# Connectors.net
KiCad netlist of a schematic drawn in Altium Designer
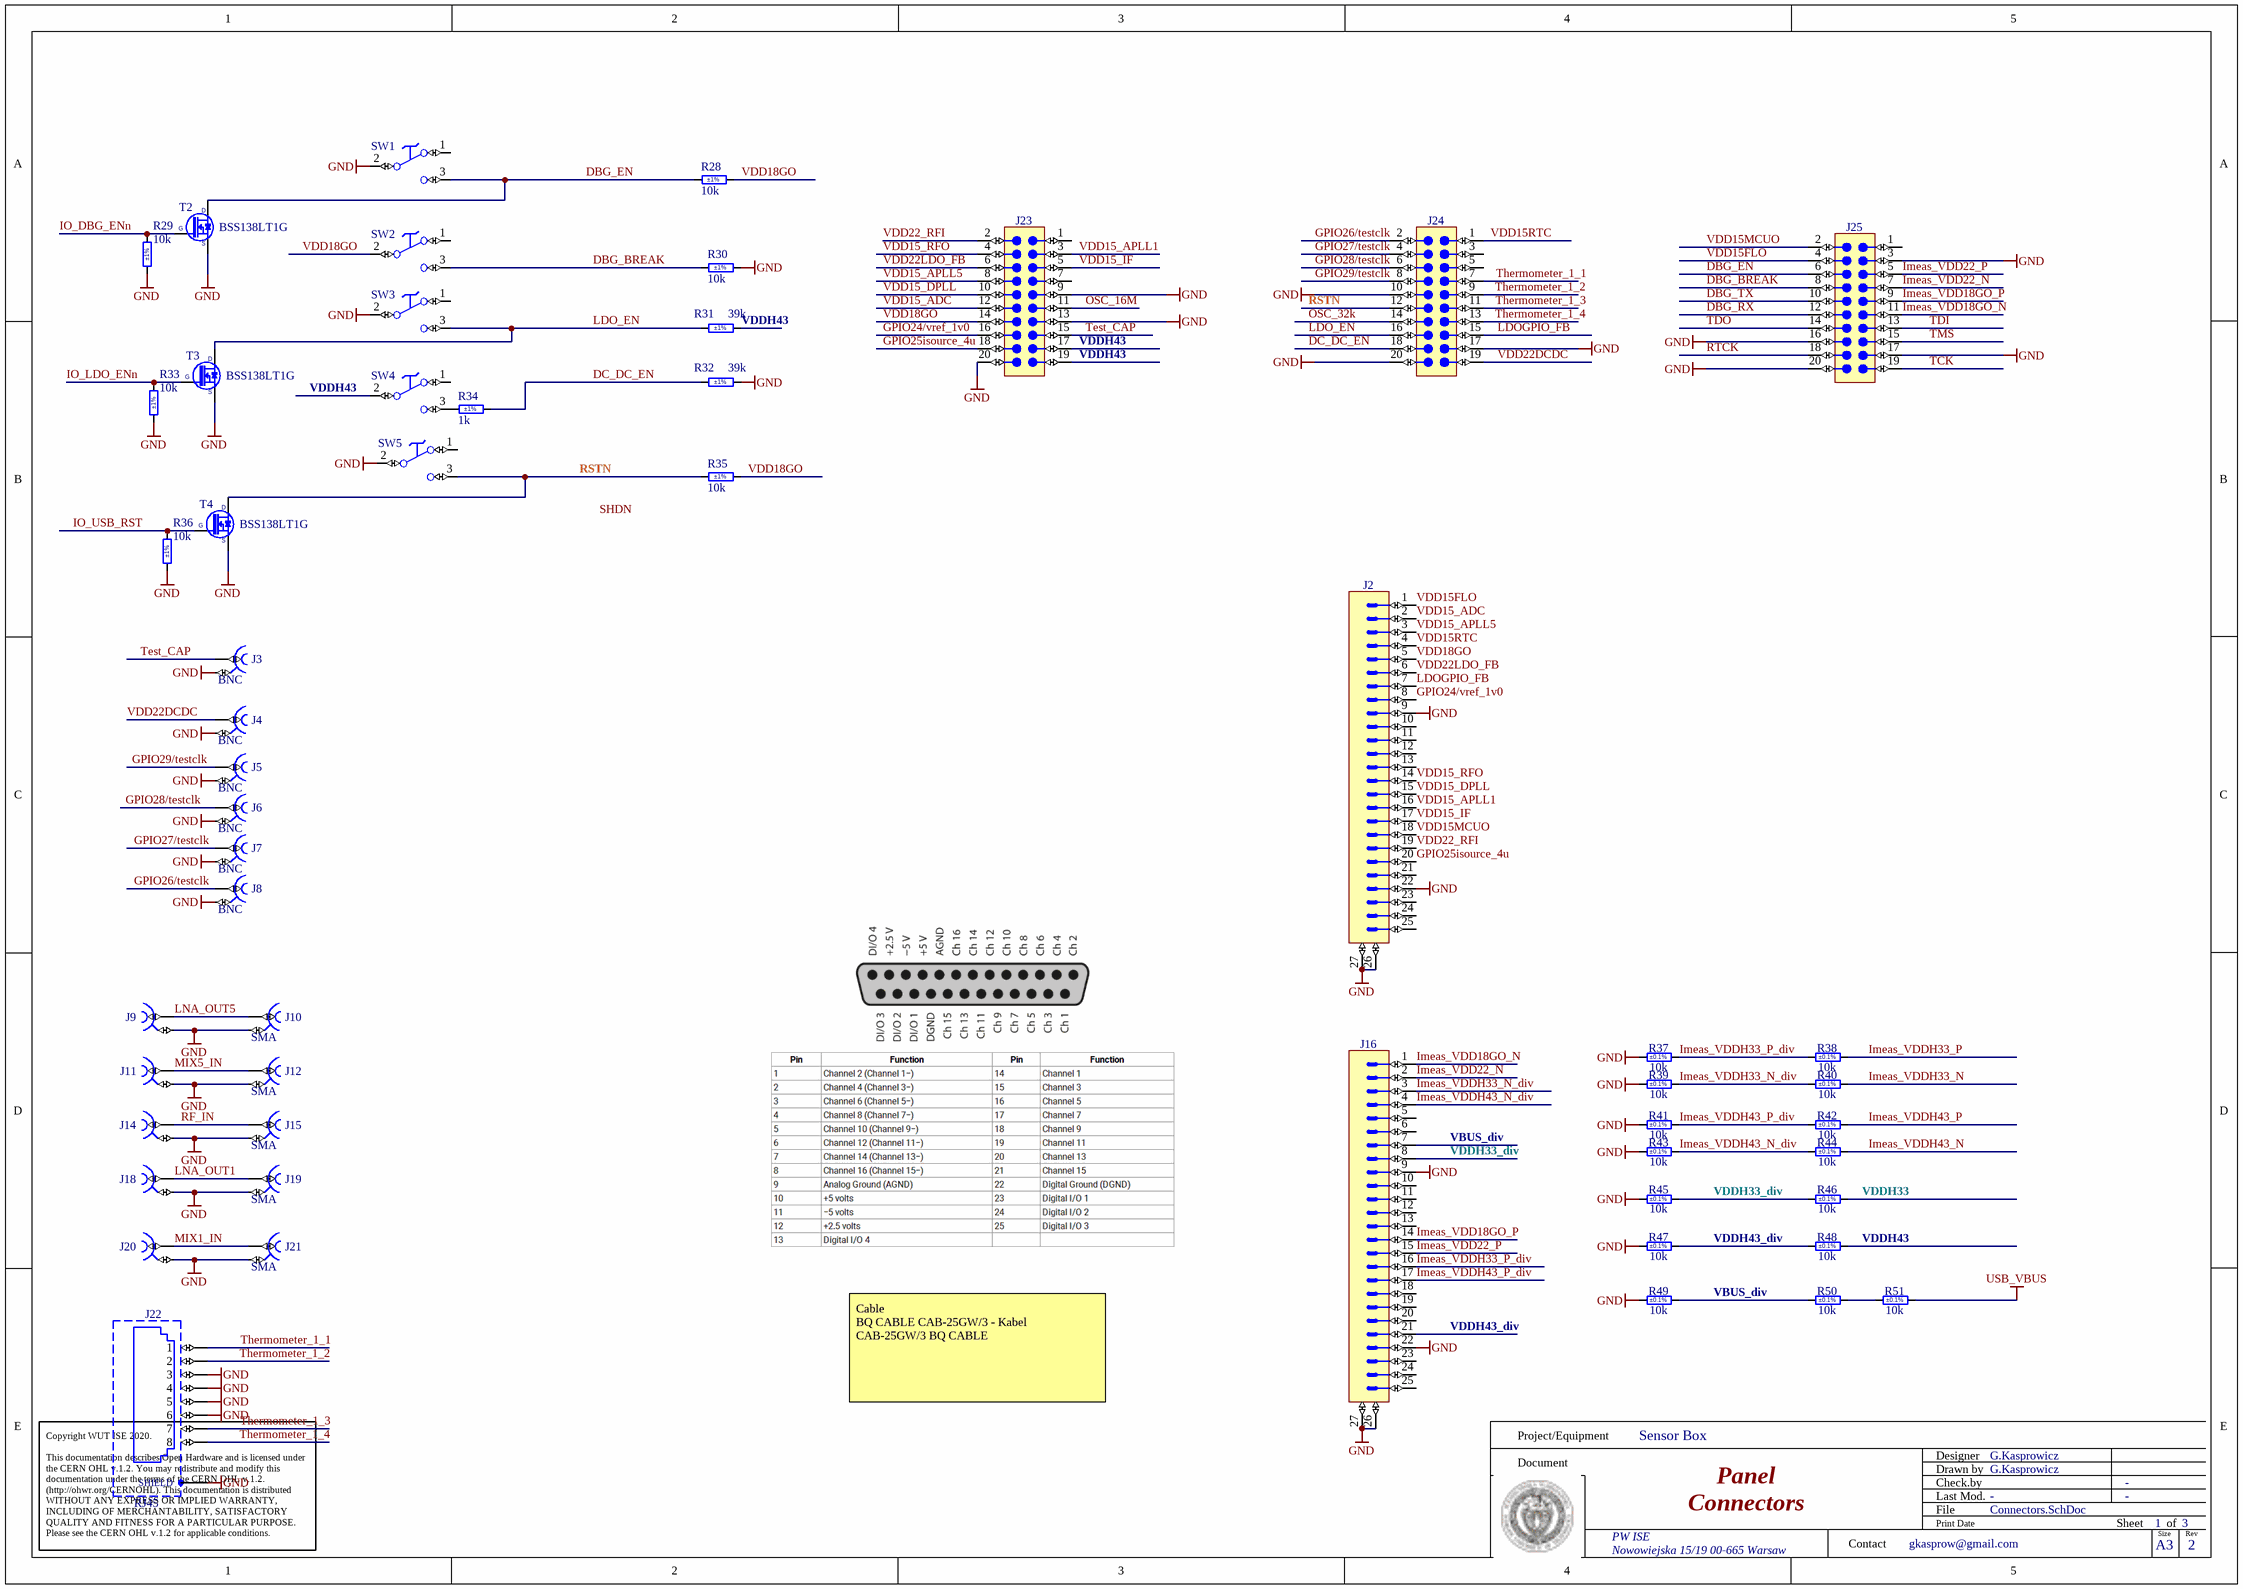
[diagram p0: Connectors.SchDoc]

(export (version "E")
  (design (tool "Eeschema 10.0.6"))
  (components
    (comp (ref "J2")
      (value "D-Sub")
      (footprint "AMPHENOL_L717SDBH25POL2RM8C309")
      (description "Connector D-sub 25 Male")
      (fields
        (field (name "PART NUMBER") "AMPHENOL_L717SDBH25POL2RM8C309")
        (field (name "MANUFACTURER") "AMPHENOL")
        (field (name "AUTHOR") "CERN DEM BC")
      )
      (libsource (lib "Connectors") (part "Connector D-sub 25 Male"))
    )
    (comp (ref "J3")
      (value "BNC")
      (footprint "TYCO_5-1634506-1")
      (fields
        (field (name "PART NUMBER") "TYCO_5-1634506-1")
        (field (name "MANUFACTURER") "TYCO ELECTRONICS")
        (field (name "MANUFACTURER PART NUMBER") "5-1634506-1")
        (field (name "AUTHOR") "CERN DEM JLC")
      )
      (libsource (lib "Connectors") (part "Coax_1Female_1Shield"))
    )
    (comp (ref "J4")
      (value "BNC")
      (footprint "TYCO_5-1634506-1")
      (fields
        (field (name "PART NUMBER") "TYCO_5-1634506-1")
        (field (name "MANUFACTURER") "TYCO ELECTRONICS")
        (field (name "MANUFACTURER PART NUMBER") "5-1634506-1")
        (field (name "AUTHOR") "CERN DEM JLC")
      )
      (libsource (lib "Connectors") (part "Coax_1Female_1Shield"))
    )
    (comp (ref "J5")
      (value "BNC")
      (footprint "TYCO_5-1634506-1")
      (fields
        (field (name "PART NUMBER") "TYCO_5-1634506-1")
        (field (name "MANUFACTURER") "TYCO ELECTRONICS")
        (field (name "MANUFACTURER PART NUMBER") "5-1634506-1")
        (field (name "AUTHOR") "CERN DEM JLC")
      )
      (libsource (lib "Connectors") (part "Coax_1Female_1Shield"))
    )
    (comp (ref "J6")
      (value "BNC")
      (footprint "TYCO_5-1634506-1")
      (fields
        (field (name "PART NUMBER") "TYCO_5-1634506-1")
        (field (name "MANUFACTURER") "TYCO ELECTRONICS")
        (field (name "MANUFACTURER PART NUMBER") "5-1634506-1")
        (field (name "AUTHOR") "CERN DEM JLC")
      )
      (libsource (lib "Connectors") (part "Coax_1Female_1Shield"))
    )
    (comp (ref "J7")
      (value "BNC")
      (footprint "TYCO_5-1634506-1")
      (fields
        (field (name "PART NUMBER") "TYCO_5-1634506-1")
        (field (name "MANUFACTURER") "TYCO ELECTRONICS")
        (field (name "MANUFACTURER PART NUMBER") "5-1634506-1")
        (field (name "AUTHOR") "CERN DEM JLC")
      )
      (libsource (lib "Connectors") (part "Coax_1Female_1Shield"))
    )
    (comp (ref "J8")
      (value "BNC")
      (footprint "TYCO_5-1634506-1")
      (fields
        (field (name "PART NUMBER") "TYCO_5-1634506-1")
        (field (name "MANUFACTURER") "TYCO ELECTRONICS")
        (field (name "MANUFACTURER PART NUMBER") "5-1634506-1")
        (field (name "AUTHOR") "CERN DEM JLC")
      )
      (libsource (lib "Connectors") (part "Coax_1Female_1Shield"))
    )
    (comp (ref "J9")
      (value "Coax_1Female_1Shield")
      (footprint "SAMTEC_MMCX-J-P-H-ST-TH1")
      (fields
        (field (name "PART NUMBER") "SAMTEC_MMCX-J-P-H-ST-TH1")
        (field (name "MANUFACTURER") "SAMTEC")
        (field (name "MANUFACTURER PART NUMBER") "MMCX-J-P-H-ST-TH1")
        (field (name "AUTHOR") "CERN DEM JLC")
      )
      (libsource (lib "") (part "Coax_1Female_1Shield_1"))
    )
    (comp (ref "J10")
      (value "SMA")
      (footprint "SAMTEC_SMA-J-P-H-ST-TH1")
      (fields
        (field (name "PART NUMBER") "SAMTEC_SMA-J-P-H-ST-TH1")
        (field (name "MANUFACTURER") "SAMTEC")
        (field (name "MANUFACTURER PART NUMBER") "SMA-J-P-H-ST-TH1")
        (field (name "AUTHOR") "CERN DEM BC")
      )
      (libsource (lib "Connectors") (part "Coax_1Female_1Shield"))
    )
    (comp (ref "J11")
      (value "Coax_1Female_1Shield")
      (footprint "SAMTEC_MMCX-J-P-H-ST-TH1")
      (fields
        (field (name "PART NUMBER") "SAMTEC_MMCX-J-P-H-ST-TH1")
        (field (name "MANUFACTURER") "SAMTEC")
        (field (name "MANUFACTURER PART NUMBER") "MMCX-J-P-H-ST-TH1")
        (field (name "AUTHOR") "CERN DEM JLC")
      )
      (libsource (lib "") (part "Coax_1Female_1Shield_1"))
    )
    (comp (ref "J12")
      (value "SMA")
      (footprint "SAMTEC_SMA-J-P-H-ST-TH1")
      (fields
        (field (name "PART NUMBER") "SAMTEC_SMA-J-P-H-ST-TH1")
        (field (name "MANUFACTURER") "SAMTEC")
        (field (name "MANUFACTURER PART NUMBER") "SMA-J-P-H-ST-TH1")
        (field (name "AUTHOR") "CERN DEM BC")
      )
      (libsource (lib "Connectors") (part "Coax_1Female_1Shield"))
    )
    (comp (ref "J14")
      (value "Coax_1Female_1Shield")
      (footprint "SAMTEC_MMCX-J-P-H-ST-TH1")
      (fields
        (field (name "PART NUMBER") "SAMTEC_MMCX-J-P-H-ST-TH1")
        (field (name "MANUFACTURER") "SAMTEC")
        (field (name "MANUFACTURER PART NUMBER") "MMCX-J-P-H-ST-TH1")
        (field (name "AUTHOR") "CERN DEM JLC")
      )
      (libsource (lib "") (part "Coax_1Female_1Shield_1"))
    )
    (comp (ref "J15")
      (value "SMA")
      (footprint "SAMTEC_SMA-J-P-H-ST-TH1")
      (fields
        (field (name "PART NUMBER") "SAMTEC_SMA-J-P-H-ST-TH1")
        (field (name "MANUFACTURER") "SAMTEC")
        (field (name "MANUFACTURER PART NUMBER") "SMA-J-P-H-ST-TH1")
        (field (name "AUTHOR") "CERN DEM BC")
      )
      (libsource (lib "Connectors") (part "Coax_1Female_1Shield"))
    )
    (comp (ref "J16")
      (value "D-Sub")
      (footprint "AMPHENOL_L717SDBH25POL2RM8C309")
      (description "Connector D-sub 25 Male")
      (fields
        (field (name "PART NUMBER") "AMPHENOL_L717SDBH25POL2RM8C309")
        (field (name "MANUFACTURER") "AMPHENOL")
        (field (name "AUTHOR") "CERN DEM BC")
      )
      (libsource (lib "Connectors") (part "Connector D-sub 25 Male"))
    )
    (comp (ref "J18")
      (value "Coax_1Female_1Shield")
      (footprint "SAMTEC_MMCX-J-P-H-ST-TH1")
      (fields
        (field (name "PART NUMBER") "SAMTEC_MMCX-J-P-H-ST-TH1")
        (field (name "MANUFACTURER") "SAMTEC")
        (field (name "MANUFACTURER PART NUMBER") "MMCX-J-P-H-ST-TH1")
        (field (name "AUTHOR") "CERN DEM JLC")
      )
      (libsource (lib "") (part "Coax_1Female_1Shield_1"))
    )
    (comp (ref "J19")
      (value "SMA")
      (footprint "SAMTEC_SMA-J-P-H-ST-TH1")
      (fields
        (field (name "PART NUMBER") "SAMTEC_SMA-J-P-H-ST-TH1")
        (field (name "MANUFACTURER") "SAMTEC")
        (field (name "MANUFACTURER PART NUMBER") "SMA-J-P-H-ST-TH1")
        (field (name "AUTHOR") "CERN DEM BC")
      )
      (libsource (lib "Connectors") (part "Coax_1Female_1Shield"))
    )
    (comp (ref "J20")
      (value "Coax_1Female_1Shield")
      (footprint "SAMTEC_MMCX-J-P-H-ST-TH1")
      (fields
        (field (name "PART NUMBER") "SAMTEC_MMCX-J-P-H-ST-TH1")
        (field (name "MANUFACTURER") "SAMTEC")
        (field (name "MANUFACTURER PART NUMBER") "MMCX-J-P-H-ST-TH1")
        (field (name "AUTHOR") "CERN DEM JLC")
      )
      (libsource (lib "") (part "Coax_1Female_1Shield_1"))
    )
    (comp (ref "J21")
      (value "SMA")
      (footprint "SAMTEC_SMA-J-P-H-ST-TH1")
      (fields
        (field (name "PART NUMBER") "SAMTEC_SMA-J-P-H-ST-TH1")
        (field (name "MANUFACTURER") "SAMTEC")
        (field (name "MANUFACTURER PART NUMBER") "SMA-J-P-H-ST-TH1")
        (field (name "AUTHOR") "CERN DEM BC")
      )
      (libsource (lib "Connectors") (part "Coax_1Female_1Shield"))
    )
    (comp (ref "J22")
      (value "RJ45")
      (footprint "TYCO_6368150-1")
      (description "Connector RJ45 + Shield")
      (fields
        (field (name "PART NUMBER") "TYCO_6368150-1")
        (field (name "MANUFACTURER") "TYCO ELECTRONICS")
        (field (name "AUTHOR") "CERN DEM MR")
      )
      (libsource (lib "Connectors") (part "Connector RJ45 + Shield"))
    )
    (comp (ref "J23")
      (value "Header 20")
      (footprint "3M_45220-600230")
      (description "Connector 20 Male")
      (fields
        (field (name "PART NUMBER") "3M_45220-600230")
        (field (name "MANUFACTURER") "3M")
        (field (name "AUTHOR") "CERN DEM MR")
      )
      (libsource (lib "Connectors") (part "Connector 20 Male"))
    )
    (comp (ref "J24")
      (value "Header 20")
      (footprint "3M_45220-600230")
      (description "Connector 20 Male")
      (fields
        (field (name "PART NUMBER") "3M_45220-600230")
        (field (name "MANUFACTURER") "3M")
        (field (name "AUTHOR") "CERN DEM MR")
      )
      (libsource (lib "Connectors") (part "Connector 20 Male"))
    )
    (comp (ref "J25")
      (value "Header 20")
      (footprint "3M_45220-600230")
      (description "Connector 20 Male")
      (fields
        (field (name "PART NUMBER") "3M_45220-600230")
        (field (name "MANUFACTURER") "3M")
        (field (name "AUTHOR") "CERN DEM MR")
      )
      (libsource (lib "Connectors") (part "Connector 20 Male"))
    )
    (comp (ref "R28")
      (value "10k")
      (footprint "RESC1005X40N")
      (description "Resistor - 1%")
      (fields
        (field (name "TOLERANCE") "±1%")
        (field (name "PART NUMBER") "R0402_10K_1%_0.0625W_100PPM")
        (field (name "POWER") "0.0625W")
        (field (name "AUTHOR") "CERN DEM JLC")
      )
      (libsource (lib "Resistors") (part "Resistor - 1%"))
    )
    (comp (ref "R29")
      (value "10k")
      (footprint "RESC1005X40N")
      (description "Resistor - 1%")
      (fields
        (field (name "TOLERANCE") "±1%")
        (field (name "PART NUMBER") "R0402_10K_1%_0.0625W_100PPM")
        (field (name "POWER") "0.0625W")
        (field (name "AUTHOR") "CERN DEM JLC")
      )
      (libsource (lib "Resistors") (part "Resistor - 1%"))
    )
    (comp (ref "R30")
      (value "10k")
      (footprint "RESC1005X40N")
      (description "Resistor - 1%")
      (fields
        (field (name "TOLERANCE") "±1%")
        (field (name "PART NUMBER") "R0402_10K_1%_0.0625W_100PPM")
        (field (name "POWER") "0.0625W")
        (field (name "AUTHOR") "CERN DEM JLC")
      )
      (libsource (lib "Resistors") (part "Resistor - 1%"))
    )
    (comp (ref "R31")
      (value "39k")
      (footprint "RESC1005X40N")
      (description "Resistor - 1%")
      (fields
        (field (name "TOLERANCE") "±1%")
        (field (name "PART NUMBER") "R0402_39K_1%_0.0625W_100PPM")
        (field (name "POWER") "0.0625W")
        (field (name "AUTHOR") "CERN DEM JLC")
      )
      (libsource (lib "Resistors") (part "Resistor - 1%"))
    )
    (comp (ref "R32")
      (value "39k")
      (footprint "RESC1005X40N")
      (description "Resistor - 1%")
      (fields
        (field (name "TOLERANCE") "±1%")
        (field (name "PART NUMBER") "R0402_39K_1%_0.0625W_100PPM")
        (field (name "POWER") "0.0625W")
        (field (name "AUTHOR") "CERN DEM JLC")
      )
      (libsource (lib "Resistors") (part "Resistor - 1%"))
    )
    (comp (ref "R33")
      (value "10k")
      (footprint "RESC1005X40N")
      (description "Resistor - 1%")
      (fields
        (field (name "TOLERANCE") "±1%")
        (field (name "PART NUMBER") "R0402_10K_1%_0.0625W_100PPM")
        (field (name "POWER") "0.0625W")
        (field (name "AUTHOR") "CERN DEM JLC")
      )
      (libsource (lib "Resistors") (part "Resistor - 1%"))
    )
    (comp (ref "R34")
      (value "1k")
      (footprint "RESC1005X40N")
      (description "Resistor - 1%")
      (fields
        (field (name "TOLERANCE") "±1%")
        (field (name "PART NUMBER") "R0402_1K_1%_0.0625W_100PPM")
        (field (name "POWER") "0.0625W")
        (field (name "AUTHOR") "CERN DEM JLC")
      )
      (libsource (lib "Resistors") (part "Resistor - 1%"))
    )
    (comp (ref "R35")
      (value "10k")
      (footprint "RESC1005X40N")
      (description "Resistor - 1%")
      (fields
        (field (name "TOLERANCE") "±1%")
        (field (name "PART NUMBER") "R0402_10K_1%_0.0625W_100PPM")
        (field (name "POWER") "0.0625W")
        (field (name "AUTHOR") "CERN DEM JLC")
      )
      (libsource (lib "Resistors") (part "Resistor - 1%"))
    )
    (comp (ref "R36")
      (value "10k")
      (footprint "RESC1005X40N")
      (description "Resistor - 1%")
      (fields
        (field (name "TOLERANCE") "±1%")
        (field (name "PART NUMBER") "R0402_10K_1%_0.0625W_100PPM")
        (field (name "POWER") "0.0625W")
        (field (name "AUTHOR") "CERN DEM JLC")
      )
      (libsource (lib "Resistors") (part "Resistor - 1%"))
    )
    (comp (ref "R37")
      (value "10k")
      (footprint "RESC1608X55N")
      (description "Resistor - 0.1%")
      (fields
        (field (name "TOLERANCE") "±0.1%")
        (field (name "PART NUMBER") "R0603_10K_0.1%_0.063W_10PPM")
        (field (name "POWER") "0.063W")
        (field (name "AUTHOR") "CERN DEM JLC")
      )
      (libsource (lib "Resistors") (part "Resistor - 0.1%"))
    )
    (comp (ref "R38")
      (value "10k")
      (footprint "RESC1608X55N")
      (description "Resistor - 0.1%")
      (fields
        (field (name "TOLERANCE") "±0.1%")
        (field (name "PART NUMBER") "R0603_10K_0.1%_0.063W_10PPM")
        (field (name "POWER") "0.063W")
        (field (name "AUTHOR") "CERN DEM JLC")
      )
      (libsource (lib "Resistors") (part "Resistor - 0.1%"))
    )
    (comp (ref "R39")
      (value "10k")
      (footprint "RESC1608X55N")
      (description "Resistor - 0.1%")
      (fields
        (field (name "TOLERANCE") "±0.1%")
        (field (name "PART NUMBER") "R0603_10K_0.1%_0.063W_10PPM")
        (field (name "POWER") "0.063W")
        (field (name "AUTHOR") "CERN DEM JLC")
      )
      (libsource (lib "Resistors") (part "Resistor - 0.1%"))
    )
    (comp (ref "R40")
      (value "10k")
      (footprint "RESC1608X55N")
      (description "Resistor - 0.1%")
      (fields
        (field (name "TOLERANCE") "±0.1%")
        (field (name "PART NUMBER") "R0603_10K_0.1%_0.063W_10PPM")
        (field (name "POWER") "0.063W")
        (field (name "AUTHOR") "CERN DEM JLC")
      )
      (libsource (lib "Resistors") (part "Resistor - 0.1%"))
    )
    (comp (ref "R41")
      (value "10k")
      (footprint "RESC1608X55N")
      (description "Resistor - 0.1%")
      (fields
        (field (name "TOLERANCE") "±0.1%")
        (field (name "PART NUMBER") "R0603_10K_0.1%_0.063W_10PPM")
        (field (name "POWER") "0.063W")
        (field (name "AUTHOR") "CERN DEM JLC")
      )
      (libsource (lib "Resistors") (part "Resistor - 0.1%"))
    )
    (comp (ref "R42")
      (value "10k")
      (footprint "RESC1608X55N")
      (description "Resistor - 0.1%")
      (fields
        (field (name "TOLERANCE") "±0.1%")
        (field (name "PART NUMBER") "R0603_10K_0.1%_0.063W_10PPM")
        (field (name "POWER") "0.063W")
        (field (name "AUTHOR") "CERN DEM JLC")
      )
      (libsource (lib "Resistors") (part "Resistor - 0.1%"))
    )
    (comp (ref "R43")
      (value "10k")
      (footprint "RESC1608X55N")
      (description "Resistor - 0.1%")
      (fields
        (field (name "TOLERANCE") "±0.1%")
        (field (name "PART NUMBER") "R0603_10K_0.1%_0.063W_10PPM")
        (field (name "POWER") "0.063W")
        (field (name "AUTHOR") "CERN DEM JLC")
      )
      (libsource (lib "Resistors") (part "Resistor - 0.1%"))
    )
    (comp (ref "R44")
      (value "10k")
      (footprint "RESC1608X55N")
      (description "Resistor - 0.1%")
      (fields
        (field (name "TOLERANCE") "±0.1%")
        (field (name "PART NUMBER") "R0603_10K_0.1%_0.063W_10PPM")
        (field (name "POWER") "0.063W")
        (field (name "AUTHOR") "CERN DEM JLC")
      )
      (libsource (lib "Resistors") (part "Resistor - 0.1%"))
    )
    (comp (ref "R45")
      (value "10k")
      (footprint "RESC1608X55N")
      (description "Resistor - 0.1%")
      (fields
        (field (name "TOLERANCE") "±0.1%")
        (field (name "PART NUMBER") "R0603_10K_0.1%_0.063W_10PPM")
        (field (name "POWER") "0.063W")
        (field (name "AUTHOR") "CERN DEM JLC")
      )
      (libsource (lib "Resistors") (part "Resistor - 0.1%"))
    )
    (comp (ref "R46")
      (value "10k")
      (footprint "RESC1608X55N")
      (description "Resistor - 0.1%")
      (fields
        (field (name "TOLERANCE") "±0.1%")
        (field (name "PART NUMBER") "R0603_10K_0.1%_0.063W_10PPM")
        (field (name "POWER") "0.063W")
        (field (name "AUTHOR") "CERN DEM JLC")
      )
      (libsource (lib "Resistors") (part "Resistor - 0.1%"))
    )
    (comp (ref "R47")
      (value "10k")
      (footprint "RESC1608X55N")
      (description "Resistor - 0.1%")
      (fields
        (field (name "TOLERANCE") "±0.1%")
        (field (name "PART NUMBER") "R0603_10K_0.1%_0.063W_10PPM")
        (field (name "POWER") "0.063W")
        (field (name "AUTHOR") "CERN DEM JLC")
      )
      (libsource (lib "Resistors") (part "Resistor - 0.1%"))
    )
    (comp (ref "R48")
      (value "10k")
      (footprint "RESC1608X55N")
      (description "Resistor - 0.1%")
      (fields
        (field (name "TOLERANCE") "±0.1%")
        (field (name "PART NUMBER") "R0603_10K_0.1%_0.063W_10PPM")
        (field (name "POWER") "0.063W")
        (field (name "AUTHOR") "CERN DEM JLC")
      )
      (libsource (lib "Resistors") (part "Resistor - 0.1%"))
    )
    (comp (ref "R49")
      (value "10k")
      (footprint "RESC1608X55N")
      (description "Resistor - 0.1%")
      (fields
        (field (name "TOLERANCE") "±0.1%")
        (field (name "PART NUMBER") "R0603_10K_0.1%_0.063W_10PPM")
        (field (name "POWER") "0.063W")
        (field (name "AUTHOR") "CERN DEM JLC")
      )
      (libsource (lib "Resistors") (part "Resistor - 0.1%"))
    )
    (comp (ref "R50")
      (value "10k")
      (footprint "RESC1608X55N")
      (description "Resistor - 0.1%")
      (fields
        (field (name "TOLERANCE") "±0.1%")
        (field (name "PART NUMBER") "R0603_10K_0.1%_0.063W_10PPM")
        (field (name "POWER") "0.063W")
        (field (name "AUTHOR") "CERN DEM JLC")
      )
      (libsource (lib "Resistors") (part "Resistor - 0.1%"))
    )
    (comp (ref "R51")
      (value "10k")
      (footprint "RESC1608X55N")
      (description "Resistor - 0.1%")
      (fields
        (field (name "TOLERANCE") "±0.1%")
        (field (name "PART NUMBER") "R0603_10K_0.1%_0.063W_10PPM")
        (field (name "POWER") "0.063W")
        (field (name "AUTHOR") "CERN DEM JLC")
      )
      (libsource (lib "Resistors") (part "Resistor - 0.1%"))
    )
    (comp (ref "SW1")
      (value "Switch")
      (footprint "SW_TYCO_1-1437575-4")
      (description "SPDT Switch")
      (fields
        (field (name "PART NUMBER") "SW_TYCO_1-1437575-4")
        (field (name "MANUFACTURER") "TYCO")
        (field (name "AUTHOR") "CERN DEM JLC")
      )
      (libsource (lib "Eletro-mechanical") (part "SW SPDT 1NC-2C-3NO"))
    )
    (comp (ref "SW2")
      (value "Switch")
      (footprint "SW_TYCO_1-1437575-4")
      (description "SPDT Switch")
      (fields
        (field (name "PART NUMBER") "SW_TYCO_1-1437575-4")
        (field (name "MANUFACTURER") "TYCO")
        (field (name "AUTHOR") "CERN DEM JLC")
      )
      (libsource (lib "Eletro-mechanical") (part "SW SPDT 1NC-2C-3NO"))
    )
    (comp (ref "SW3")
      (value "Switch")
      (footprint "SW_TYCO_1-1437575-4")
      (description "SPDT Switch")
      (fields
        (field (name "PART NUMBER") "SW_TYCO_1-1437575-4")
        (field (name "MANUFACTURER") "TYCO")
        (field (name "AUTHOR") "CERN DEM JLC")
      )
      (libsource (lib "Eletro-mechanical") (part "SW SPDT 1NC-2C-3NO"))
    )
    (comp (ref "SW4")
      (value "Switch")
      (footprint "SW_TYCO_1-1437575-4")
      (description "SPDT Switch")
      (fields
        (field (name "PART NUMBER") "SW_TYCO_1-1437575-4")
        (field (name "MANUFACTURER") "TYCO")
        (field (name "AUTHOR") "CERN DEM JLC")
      )
      (libsource (lib "Eletro-mechanical") (part "SW SPDT 1NC-2C-3NO"))
    )
    (comp (ref "SW5")
      (value "Switch")
      (footprint "SW_TYCO_1-1437575-4")
      (description "SPDT Switch")
      (fields
        (field (name "PART NUMBER") "SW_TYCO_1-1437575-4")
        (field (name "MANUFACTURER") "TYCO")
        (field (name "AUTHOR") "CERN DEM JLC")
      )
      (libsource (lib "Eletro-mechanical") (part "SW SPDT 1NC-2C-3NO"))
    )
    (comp (ref "T2")
      (value "BSS138LT1G")
      (footprint "SOT95P240X110-3N")
      (description "N-CHANNEL MOSFET WITH DIODE")
      (fields (field (name "MANUFACTURER") "ON SEMICONDUCTOR") (field (name "AUTHOR") "CERN DEM JLC"))
      (libsource (lib "ICs And Semiconductors") (part "N-MOSFET-D 1G 2S 3D"))
    )
    (comp (ref "T3")
      (value "BSS138LT1G")
      (footprint "SOT95P240X110-3N")
      (description "N-CHANNEL MOSFET WITH DIODE")
      (fields (field (name "MANUFACTURER") "ON SEMICONDUCTOR") (field (name "AUTHOR") "CERN DEM JLC"))
      (libsource (lib "ICs And Semiconductors") (part "N-MOSFET-D 1G 2S 3D"))
    )
    (comp (ref "T4")
      (value "BSS138LT1G")
      (footprint "SOT95P240X110-3N")
      (description "N-CHANNEL MOSFET WITH DIODE")
      (fields (field (name "MANUFACTURER") "ON SEMICONDUCTOR") (field (name "AUTHOR") "CERN DEM JLC"))
      (libsource (lib "ICs And Semiconductors") (part "N-MOSFET-D 1G 2S 3D"))
    )
  )
  (nets
    (net (code "1") (name "/DBG_BREAK") (class "Default")
      (node (ref "J25") (pin "8") (pinfunction "8_8") (pintype "bidirectional"))
      (node (ref "R30") (pin "1") (pinfunction "1_1") (pintype "passive"))
      (node (ref "SW2") (pin "3") (pinfunction "NO_3") (pintype "bidirectional"))
    )
    (net (code "2") (name "/DBG_EN") (class "Default")
      (node (ref "J25") (pin "6") (pinfunction "6_6") (pintype "bidirectional"))
      (node (ref "R28") (pin "1") (pinfunction "1_1") (pintype "passive"))
      (node (ref "SW1") (pin "3") (pinfunction "NO_3") (pintype "bidirectional"))
      (node (ref "T2") (pin "3") (pinfunction "D_3") (pintype "passive"))
    )
    (net (code "3") (name "/DBG_RX") (class "Default")
      (node (ref "J25") (pin "12") (pinfunction "12_12") (pintype "bidirectional"))
    )
    (net (code "4") (name "/DBG_TX") (class "Default")
      (node (ref "J25") (pin "10") (pinfunction "10_10") (pintype "bidirectional"))
    )
    (net (code "5") (name "/DC_DC_EN") (class "Default")
      (node (ref "J24") (pin "18") (pinfunction "18_18") (pintype "bidirectional"))
      (node (ref "R32") (pin "2") (pinfunction "2_2") (pintype "passive"))
      (node (ref "R34") (pin "1") (pinfunction "1_1") (pintype "passive"))
    )
    (net (code "6") (name "/GPIO24{slash}vref_1v0") (class "Default")
      (node (ref "J2") (pin "8") (pinfunction "8_8") (pintype "bidirectional"))
      (node (ref "J23") (pin "16") (pinfunction "16_16") (pintype "bidirectional"))
    )
    (net (code "7") (name "/GPIO25isource_4u") (class "Default")
      (node (ref "J2") (pin "20") (pinfunction "20_20") (pintype "bidirectional"))
      (node (ref "J23") (pin "18") (pinfunction "18_18") (pintype "bidirectional"))
    )
    (net (code "8") (name "/GPIO26{slash}testclk") (class "Default")
      (node (ref "J24") (pin "2") (pinfunction "2_2") (pintype "bidirectional"))
      (node (ref "J8") (pin "1") (pinfunction "1_1") (pintype "bidirectional"))
    )
    (net (code "9") (name "/GPIO27{slash}testclk") (class "Default")
      (node (ref "J24") (pin "4") (pinfunction "4_4") (pintype "bidirectional"))
      (node (ref "J7") (pin "1") (pinfunction "1_1") (pintype "bidirectional"))
    )
    (net (code "10") (name "/GPIO28{slash}testclk") (class "Default")
      (node (ref "J24") (pin "6") (pinfunction "6_6") (pintype "bidirectional"))
      (node (ref "J6") (pin "1") (pinfunction "1_1") (pintype "bidirectional"))
    )
    (net (code "11") (name "/GPIO29{slash}testclk") (class "Default")
      (node (ref "J24") (pin "8") (pinfunction "8_8") (pintype "bidirectional"))
      (node (ref "J5") (pin "1") (pinfunction "1_1") (pintype "bidirectional"))
    )
    (net (code "12") (name "/IO_DBG_ENn") (class "Default")
      (node (ref "R29") (pin "1") (pinfunction "1_1") (pintype "passive"))
      (node (ref "T2") (pin "1") (pinfunction "G_1") (pintype "passive"))
    )
    (net (code "13") (name "/IO_LDO_ENn") (class "Default")
      (node (ref "R33") (pin "1") (pinfunction "1_1") (pintype "passive"))
      (node (ref "T3") (pin "1") (pinfunction "G_1") (pintype "passive"))
    )
    (net (code "14") (name "/IO_USB_RST") (class "Default")
      (node (ref "R36") (pin "1") (pinfunction "1_1") (pintype "passive"))
      (node (ref "T4") (pin "1") (pinfunction "G_1") (pintype "passive"))
    )
    (net (code "15") (name "/Imeas_VDD18GO_N") (class "Default")
      (node (ref "J16") (pin "1") (pinfunction "1_1") (pintype "bidirectional"))
      (node (ref "J25") (pin "11") (pinfunction "11_11") (pintype "bidirectional"))
    )
    (net (code "16") (name "/Imeas_VDD18GO_P") (class "Default")
      (node (ref "J16") (pin "14") (pinfunction "14_14") (pintype "bidirectional"))
      (node (ref "J25") (pin "9") (pinfunction "9_9") (pintype "bidirectional"))
    )
    (net (code "17") (name "/Imeas_VDD22_N") (class "Default")
      (node (ref "J16") (pin "2") (pinfunction "2_2") (pintype "bidirectional"))
      (node (ref "J25") (pin "7") (pinfunction "7_7") (pintype "bidirectional"))
    )
    (net (code "18") (name "/Imeas_VDD22_P") (class "Default")
      (node (ref "J16") (pin "15") (pinfunction "15_15") (pintype "bidirectional"))
      (node (ref "J25") (pin "5") (pinfunction "5_5") (pintype "bidirectional"))
    )
    (net (code "19") (name "/Imeas_VDDH33_N") (class "Default")
      (node (ref "R40") (pin "2") (pinfunction "2_2") (pintype "passive"))
    )
    (net (code "20") (name "/Imeas_VDDH33_N_div") (class "Default")
      (node (ref "J16") (pin "3") (pinfunction "3_3") (pintype "bidirectional"))
      (node (ref "R39") (pin "2") (pinfunction "2_2") (pintype "passive"))
      (node (ref "R40") (pin "1") (pinfunction "1_1") (pintype "passive"))
    )
    (net (code "21") (name "/Imeas_VDDH33_P") (class "Default")
      (node (ref "R38") (pin "2") (pinfunction "2_2") (pintype "passive"))
    )
    (net (code "22") (name "/Imeas_VDDH33_P_div") (class "Default")
      (node (ref "J16") (pin "16") (pinfunction "16_16") (pintype "bidirectional"))
      (node (ref "R37") (pin "2") (pinfunction "2_2") (pintype "passive"))
      (node (ref "R38") (pin "1") (pinfunction "1_1") (pintype "passive"))
    )
    (net (code "23") (name "/Imeas_VDDH43_N") (class "Default")
      (node (ref "R44") (pin "2") (pinfunction "2_2") (pintype "passive"))
    )
    (net (code "24") (name "/Imeas_VDDH43_N_div") (class "Default")
      (node (ref "J16") (pin "4") (pinfunction "4_4") (pintype "bidirectional"))
      (node (ref "R43") (pin "2") (pinfunction "2_2") (pintype "passive"))
      (node (ref "R44") (pin "1") (pinfunction "1_1") (pintype "passive"))
    )
    (net (code "25") (name "/Imeas_VDDH43_P") (class "Default")
      (node (ref "R42") (pin "2") (pinfunction "2_2") (pintype "passive"))
    )
    (net (code "26") (name "/Imeas_VDDH43_P_div") (class "Default")
      (node (ref "J16") (pin "17") (pinfunction "17_17") (pintype "bidirectional"))
      (node (ref "R41") (pin "2") (pinfunction "2_2") (pintype "passive"))
      (node (ref "R42") (pin "1") (pinfunction "1_1") (pintype "passive"))
    )
    (net (code "27") (name "/LDOGPIO_FB") (class "Default")
      (node (ref "J2") (pin "7") (pinfunction "7_7") (pintype "bidirectional"))
      (node (ref "J24") (pin "15") (pinfunction "15_15") (pintype "bidirectional"))
    )
    (net (code "28") (name "/LDO_EN") (class "Default")
      (node (ref "J24") (pin "16") (pinfunction "16_16") (pintype "bidirectional"))
      (node (ref "R31") (pin "2") (pinfunction "2_2") (pintype "passive"))
      (node (ref "SW3") (pin "3") (pinfunction "NO_3") (pintype "bidirectional"))
      (node (ref "T3") (pin "3") (pinfunction "D_3") (pintype "passive"))
    )
    (net (code "29") (name "/LNA_OUT1") (class "Default")
      (node (ref "J18") (pin "1") (pinfunction "1_1") (pintype "bidirectional"))
      (node (ref "J19") (pin "1") (pinfunction "1_1") (pintype "bidirectional"))
    )
    (net (code "30") (name "/LNA_OUT5") (class "Default")
      (node (ref "J10") (pin "1") (pinfunction "1_1") (pintype "bidirectional"))
      (node (ref "J9") (pin "1") (pinfunction "1_1") (pintype "bidirectional"))
    )
    (net (code "31") (name "/MIX1_IN") (class "Default")
      (node (ref "J20") (pin "1") (pinfunction "1_1") (pintype "bidirectional"))
      (node (ref "J21") (pin "1") (pinfunction "1_1") (pintype "bidirectional"))
    )
    (net (code "32") (name "/MIX5_IN") (class "Default")
      (node (ref "J11") (pin "1") (pinfunction "1_1") (pintype "bidirectional"))
      (node (ref "J12") (pin "1") (pinfunction "1_1") (pintype "bidirectional"))
    )
    (net (code "33") (name "/OSC_16M") (class "Default")
      (node (ref "J23") (pin "11") (pinfunction "11_11") (pintype "bidirectional"))
    )
    (net (code "34") (name "/OSC_32k") (class "Default")
      (node (ref "J24") (pin "14") (pinfunction "14_14") (pintype "bidirectional"))
    )
    (net (code "35") (name "/RF_IN") (class "Default")
      (node (ref "J14") (pin "1") (pinfunction "1_1") (pintype "bidirectional"))
      (node (ref "J15") (pin "1") (pinfunction "1_1") (pintype "bidirectional"))
    )
    (net (code "36") (name "/RSTN") (class "Default")
      (node (ref "J24") (pin "12") (pinfunction "12_12") (pintype "bidirectional"))
      (node (ref "R35") (pin "1") (pinfunction "1_1") (pintype "passive"))
      (node (ref "SW5") (pin "3") (pinfunction "NO_3") (pintype "bidirectional"))
      (node (ref "T4") (pin "3") (pinfunction "D_3") (pintype "passive"))
    )
    (net (code "37") (name "/RTCK") (class "Default")
      (node (ref "J25") (pin "18") (pinfunction "18_18") (pintype "bidirectional"))
    )
    (net (code "39") (name "/TCK") (class "Default")
      (node (ref "J25") (pin "19") (pinfunction "19_19") (pintype "bidirectional"))
    )
    (net (code "40") (name "/TDI") (class "Default")
      (node (ref "J25") (pin "13") (pinfunction "13_13") (pintype "bidirectional"))
    )
    (net (code "41") (name "/TDO") (class "Default")
      (node (ref "J25") (pin "14") (pinfunction "14_14") (pintype "bidirectional"))
    )
    (net (code "42") (name "/TMS") (class "Default")
      (node (ref "J25") (pin "15") (pinfunction "15_15") (pintype "bidirectional"))
    )
    (net (code "43") (name "/Test_CAP") (class "Default")
      (node (ref "J23") (pin "15") (pinfunction "15_15") (pintype "bidirectional"))
      (node (ref "J3") (pin "1") (pinfunction "1_1") (pintype "bidirectional"))
    )
    (net (code "44") (name "/Thermometer_1_1") (class "Default")
      (node (ref "J22") (pin "1") (pinfunction "1_1") (pintype "bidirectional"))
      (node (ref "J24") (pin "7") (pinfunction "7_7") (pintype "bidirectional"))
    )
    (net (code "45") (name "/Thermometer_1_2") (class "Default")
      (node (ref "J22") (pin "2") (pinfunction "2_2") (pintype "bidirectional"))
      (node (ref "J24") (pin "9") (pinfunction "9_9") (pintype "bidirectional"))
    )
    (net (code "46") (name "/Thermometer_1_3") (class "Default")
      (node (ref "J22") (pin "7") (pinfunction "7_7") (pintype "bidirectional"))
      (node (ref "J24") (pin "11") (pinfunction "11_11") (pintype "bidirectional"))
    )
    (net (code "47") (name "/Thermometer_1_4") (class "Default")
      (node (ref "J22") (pin "8") (pinfunction "8_8") (pintype "bidirectional"))
      (node (ref "J24") (pin "13") (pinfunction "13_13") (pintype "bidirectional"))
    )
    (net (code "48") (name "/VBUS_div") (class "Default")
      (node (ref "J16") (pin "7") (pinfunction "7_7") (pintype "bidirectional"))
      (node (ref "R49") (pin "2") (pinfunction "2_2") (pintype "passive"))
      (node (ref "R50") (pin "1") (pinfunction "1_1") (pintype "passive"))
    )
    (net (code "49") (name "/VDD15FLO") (class "Default")
      (node (ref "J2") (pin "1") (pinfunction "1_1") (pintype "bidirectional"))
      (node (ref "J25") (pin "4") (pinfunction "4_4") (pintype "bidirectional"))
    )
    (net (code "50") (name "/VDD15MCUO") (class "Default")
      (node (ref "J2") (pin "18") (pinfunction "18_18") (pintype "bidirectional"))
      (node (ref "J25") (pin "2") (pinfunction "2_2") (pintype "bidirectional"))
    )
    (net (code "51") (name "/VDD15RTC") (class "Default")
      (node (ref "J2") (pin "4") (pinfunction "4_4") (pintype "bidirectional"))
      (node (ref "J24") (pin "1") (pinfunction "1_1") (pintype "bidirectional"))
    )
    (net (code "52") (name "/VDD15_ADC") (class "Default")
      (node (ref "J2") (pin "2") (pinfunction "2_2") (pintype "bidirectional"))
      (node (ref "J23") (pin "12") (pinfunction "12_12") (pintype "bidirectional"))
    )
    (net (code "53") (name "/VDD15_APLL1") (class "Default")
      (node (ref "J2") (pin "16") (pinfunction "16_16") (pintype "bidirectional"))
      (node (ref "J23") (pin "3") (pinfunction "3_3") (pintype "bidirectional"))
    )
    (net (code "54") (name "/VDD15_APLL5") (class "Default")
      (node (ref "J2") (pin "3") (pinfunction "3_3") (pintype "bidirectional"))
      (node (ref "J23") (pin "8") (pinfunction "8_8") (pintype "bidirectional"))
    )
    (net (code "55") (name "/VDD15_DPLL") (class "Default")
      (node (ref "J2") (pin "15") (pinfunction "15_15") (pintype "bidirectional"))
      (node (ref "J23") (pin "10") (pinfunction "10_10") (pintype "bidirectional"))
    )
    (net (code "56") (name "/VDD15_IF") (class "Default")
      (node (ref "J2") (pin "17") (pinfunction "17_17") (pintype "bidirectional"))
      (node (ref "J23") (pin "5") (pinfunction "5_5") (pintype "bidirectional"))
    )
    (net (code "57") (name "/VDD15_RFO") (class "Default")
      (node (ref "J2") (pin "14") (pinfunction "14_14") (pintype "bidirectional"))
      (node (ref "J23") (pin "4") (pinfunction "4_4") (pintype "bidirectional"))
    )
    (net (code "58") (name "/VDD18GO") (class "Default")
      (node (ref "J2") (pin "5") (pinfunction "5_5") (pintype "bidirectional"))
      (node (ref "J23") (pin "14") (pinfunction "14_14") (pintype "bidirectional"))
      (node (ref "R28") (pin "2") (pinfunction "2_2") (pintype "passive"))
      (node (ref "R35") (pin "2") (pinfunction "2_2") (pintype "passive"))
      (node (ref "SW2") (pin "2") (pinfunction "C_2") (pintype "bidirectional"))
    )
    (net (code "59") (name "/VDD22DCDC") (class "Default")
      (node (ref "J24") (pin "19") (pinfunction "19_19") (pintype "bidirectional"))
      (node (ref "J4") (pin "1") (pinfunction "1_1") (pintype "bidirectional"))
    )
    (net (code "60") (name "/VDD22LDO_FB") (class "Default")
      (node (ref "J2") (pin "6") (pinfunction "6_6") (pintype "bidirectional"))
      (node (ref "J23") (pin "6") (pinfunction "6_6") (pintype "bidirectional"))
    )
    (net (code "61") (name "/VDD22_RFI") (class "Default")
      (node (ref "J2") (pin "19") (pinfunction "19_19") (pintype "bidirectional"))
      (node (ref "J23") (pin "2") (pinfunction "2_2") (pintype "bidirectional"))
    )
    (net (code "62") (name "/VDDH33") (class "Default")
      (node (ref "R46") (pin "2") (pinfunction "2_2") (pintype "passive"))
    )
    (net (code "63") (name "/VDDH33_div") (class "Default")
      (node (ref "J16") (pin "8") (pinfunction "8_8") (pintype "bidirectional"))
      (node (ref "R45") (pin "2") (pinfunction "2_2") (pintype "passive"))
      (node (ref "R46") (pin "1") (pinfunction "1_1") (pintype "passive"))
    )
    (net (code "64") (name "/VDDH43") (class "Default")
      (node (ref "J23") (pin "17") (pinfunction "17_17") (pintype "bidirectional"))
      (node (ref "J23") (pin "19") (pinfunction "19_19") (pintype "bidirectional"))
      (node (ref "R31") (pin "1") (pinfunction "1_1") (pintype "passive"))
      (node (ref "R48") (pin "2") (pinfunction "2_2") (pintype "passive"))
      (node (ref "SW4") (pin "2") (pinfunction "C_2") (pintype "bidirectional"))
    )
    (net (code "65") (name "/VDDH43_div") (class "Default")
      (node (ref "J16") (pin "21") (pinfunction "21_21") (pintype "bidirectional"))
      (node (ref "R47") (pin "2") (pinfunction "2_2") (pintype "passive"))
      (node (ref "R48") (pin "1") (pinfunction "1_1") (pintype "passive"))
    )
    (net (code "66") (name "GND") (class "Default")
      (node (ref "J10") (pin "2") (pinfunction "2_2") (pintype "bidirectional"))
      (node (ref "J11") (pin "2") (pinfunction "2_2") (pintype "bidirectional"))
      (node (ref "J12") (pin "2") (pinfunction "2_2") (pintype "bidirectional"))
      (node (ref "J14") (pin "2") (pinfunction "2_2") (pintype "bidirectional"))
      (node (ref "J15") (pin "2") (pinfunction "2_2") (pintype "bidirectional"))
      (node (ref "J16") (pin "22") (pinfunction "22_22") (pintype "bidirectional"))
      (node (ref "J16") (pin "26") (pinfunction "26_26") (pintype "bidirectional"))
      (node (ref "J16") (pin "27") (pinfunction "27_27") (pintype "bidirectional"))
      (node (ref "J16") (pin "9") (pinfunction "9_9") (pintype "bidirectional"))
      (node (ref "J18") (pin "2") (pinfunction "2_2") (pintype "bidirectional"))
      (node (ref "J19") (pin "2") (pinfunction "2_2") (pintype "bidirectional"))
      (node (ref "J2") (pin "22") (pinfunction "22_22") (pintype "bidirectional"))
      (node (ref "J2") (pin "26") (pinfunction "26_26") (pintype "bidirectional"))
      (node (ref "J2") (pin "27") (pinfunction "27_27") (pintype "bidirectional"))
      (node (ref "J2") (pin "9") (pinfunction "9_9") (pintype "bidirectional"))
      (node (ref "J20") (pin "2") (pinfunction "2_2") (pintype "bidirectional"))
      (node (ref "J21") (pin "2") (pinfunction "2_2") (pintype "bidirectional"))
      (node (ref "J22") (pin "3") (pinfunction "3_3") (pintype "bidirectional"))
      (node (ref "J22") (pin "4") (pinfunction "4_4") (pintype "bidirectional"))
      (node (ref "J22") (pin "5") (pinfunction "5_5") (pintype "bidirectional"))
      (node (ref "J22") (pin "6") (pinfunction "6_6") (pintype "bidirectional"))
      (node (ref "J22") (pin "SHIELD") (pinfunction "SHIELD_SHIELD") (pintype "passive"))
      (node (ref "J23") (pin "13") (pinfunction "13_13") (pintype "bidirectional"))
      (node (ref "J23") (pin "20") (pinfunction "20_20") (pintype "bidirectional"))
      (node (ref "J23") (pin "9") (pinfunction "9_9") (pintype "bidirectional"))
      (node (ref "J24") (pin "10") (pinfunction "10_10") (pintype "bidirectional"))
      (node (ref "J24") (pin "17") (pinfunction "17_17") (pintype "bidirectional"))
      (node (ref "J24") (pin "20") (pinfunction "20_20") (pintype "bidirectional"))
      (node (ref "J25") (pin "16") (pinfunction "16_16") (pintype "bidirectional"))
      (node (ref "J25") (pin "17") (pinfunction "17_17") (pintype "bidirectional"))
      (node (ref "J25") (pin "20") (pinfunction "20_20") (pintype "bidirectional"))
      (node (ref "J25") (pin "3") (pinfunction "3_3") (pintype "bidirectional"))
      (node (ref "J3") (pin "2") (pinfunction "2_2") (pintype "bidirectional"))
      (node (ref "J4") (pin "2") (pinfunction "2_2") (pintype "bidirectional"))
      (node (ref "J5") (pin "2") (pinfunction "2_2") (pintype "bidirectional"))
      (node (ref "J6") (pin "2") (pinfunction "2_2") (pintype "bidirectional"))
      (node (ref "J7") (pin "2") (pinfunction "2_2") (pintype "bidirectional"))
      (node (ref "J8") (pin "2") (pinfunction "2_2") (pintype "bidirectional"))
      (node (ref "J9") (pin "2") (pinfunction "2_2") (pintype "bidirectional"))
      (node (ref "R29") (pin "2") (pinfunction "2_2") (pintype "passive"))
      (node (ref "R30") (pin "2") (pinfunction "2_2") (pintype "passive"))
      (node (ref "R32") (pin "1") (pinfunction "1_1") (pintype "passive"))
      (node (ref "R33") (pin "2") (pinfunction "2_2") (pintype "passive"))
      (node (ref "R36") (pin "2") (pinfunction "2_2") (pintype "passive"))
      (node (ref "R37") (pin "1") (pinfunction "1_1") (pintype "passive"))
      (node (ref "R39") (pin "1") (pinfunction "1_1") (pintype "passive"))
      (node (ref "R41") (pin "1") (pinfunction "1_1") (pintype "passive"))
      (node (ref "R43") (pin "1") (pinfunction "1_1") (pintype "passive"))
      (node (ref "R45") (pin "1") (pinfunction "1_1") (pintype "passive"))
      (node (ref "R47") (pin "1") (pinfunction "1_1") (pintype "passive"))
      (node (ref "R49") (pin "1") (pinfunction "1_1") (pintype "passive"))
      (node (ref "SW1") (pin "2") (pinfunction "C_2") (pintype "bidirectional"))
      (node (ref "SW3") (pin "2") (pinfunction "C_2") (pintype "bidirectional"))
      (node (ref "SW5") (pin "2") (pinfunction "C_2") (pintype "bidirectional"))
      (node (ref "T2") (pin "2") (pinfunction "S_2") (pintype "passive"))
      (node (ref "T3") (pin "2") (pinfunction "S_2") (pintype "passive"))
      (node (ref "T4") (pin "2") (pinfunction "S_2") (pintype "passive"))
    )
    (net (code "67") (name "Net-(R50-Pad2)") (class "Default")
      (node (ref "R50") (pin "2") (pinfunction "2_2") (pintype "passive"))
      (node (ref "R51") (pin "1") (pinfunction "1_1") (pintype "passive"))
    )
    (net (code "68") (name "Net-(SW4-NO)") (class "Default")
      (node (ref "R34") (pin "2") (pinfunction "2_2") (pintype "passive"))
      (node (ref "SW4") (pin "3") (pinfunction "NO_3") (pintype "bidirectional"))
    )
    (net (code "69") (name "USB_VBUS") (class "Default")
      (node (ref "R51") (pin "2") (pinfunction "2_2") (pintype "passive"))
    )
    (net (code "70") (name "unconnected-(J2-Pad10)") (class "Default")
      (node (ref "J2") (pin "10") (pinfunction "10_10") (pintype "bidirectional"))
    )
    (net (code "71") (name "unconnected-(J2-Pad11)") (class "Default")
      (node (ref "J2") (pin "11") (pinfunction "11_11") (pintype "bidirectional"))
    )
    (net (code "72") (name "unconnected-(J2-Pad12)") (class "Default")
      (node (ref "J2") (pin "12") (pinfunction "12_12") (pintype "bidirectional"))
    )
    (net (code "73") (name "unconnected-(J2-Pad13)") (class "Default")
      (node (ref "J2") (pin "13") (pinfunction "13_13") (pintype "bidirectional"))
    )
    (net (code "74") (name "unconnected-(J2-Pad21)") (class "Default")
      (node (ref "J2") (pin "21") (pinfunction "21_21") (pintype "bidirectional"))
    )
    (net (code "75") (name "unconnected-(J2-Pad23)") (class "Default")
      (node (ref "J2") (pin "23") (pinfunction "23_23") (pintype "bidirectional"))
    )
    (net (code "76") (name "unconnected-(J2-Pad24)") (class "Default")
      (node (ref "J2") (pin "24") (pinfunction "24_24") (pintype "bidirectional"))
    )
    (net (code "77") (name "unconnected-(J2-Pad25)") (class "Default")
      (node (ref "J2") (pin "25") (pinfunction "25_25") (pintype "bidirectional"))
    )
    (net (code "78") (name "unconnected-(J16-Pad5)") (class "Default")
      (node (ref "J16") (pin "5") (pinfunction "5_5") (pintype "bidirectional"))
    )
    (net (code "79") (name "unconnected-(J16-Pad6)") (class "Default")
      (node (ref "J16") (pin "6") (pinfunction "6_6") (pintype "bidirectional"))
    )
    (net (code "80") (name "unconnected-(J16-Pad10)") (class "Default")
      (node (ref "J16") (pin "10") (pinfunction "10_10") (pintype "bidirectional"))
    )
    (net (code "81") (name "unconnected-(J16-Pad11)") (class "Default")
      (node (ref "J16") (pin "11") (pinfunction "11_11") (pintype "bidirectional"))
    )
    (net (code "82") (name "unconnected-(J16-Pad12)") (class "Default")
      (node (ref "J16") (pin "12") (pinfunction "12_12") (pintype "bidirectional"))
    )
    (net (code "83") (name "unconnected-(J16-Pad13)") (class "Default")
      (node (ref "J16") (pin "13") (pinfunction "13_13") (pintype "bidirectional"))
    )
    (net (code "84") (name "unconnected-(J16-Pad18)") (class "Default")
      (node (ref "J16") (pin "18") (pinfunction "18_18") (pintype "bidirectional"))
    )
    (net (code "85") (name "unconnected-(J16-Pad19)") (class "Default")
      (node (ref "J16") (pin "19") (pinfunction "19_19") (pintype "bidirectional"))
    )
    (net (code "86") (name "unconnected-(J16-Pad20)") (class "Default")
      (node (ref "J16") (pin "20") (pinfunction "20_20") (pintype "bidirectional"))
    )
    (net (code "87") (name "unconnected-(J16-Pad23)") (class "Default")
      (node (ref "J16") (pin "23") (pinfunction "23_23") (pintype "bidirectional"))
    )
    (net (code "88") (name "unconnected-(J16-Pad24)") (class "Default")
      (node (ref "J16") (pin "24") (pinfunction "24_24") (pintype "bidirectional"))
    )
    (net (code "89") (name "unconnected-(J16-Pad25)") (class "Default")
      (node (ref "J16") (pin "25") (pinfunction "25_25") (pintype "bidirectional"))
    )
    (net (code "90") (name "unconnected-(J23-Pad1)") (class "Default")
      (node (ref "J23") (pin "1") (pinfunction "1_1") (pintype "bidirectional"))
    )
    (net (code "91") (name "unconnected-(J23-Pad7)") (class "Default")
      (node (ref "J23") (pin "7") (pinfunction "7_7") (pintype "bidirectional"))
    )
    (net (code "92") (name "unconnected-(J24-Pad3)") (class "Default")
      (node (ref "J24") (pin "3") (pinfunction "3_3") (pintype "bidirectional"))
    )
    (net (code "93") (name "unconnected-(J24-Pad5)") (class "Default")
      (node (ref "J24") (pin "5") (pinfunction "5_5") (pintype "bidirectional"))
    )
    (net (code "94") (name "unconnected-(J25-Pad1)") (class "Default")
      (node (ref "J25") (pin "1") (pinfunction "1_1") (pintype "bidirectional"))
    )
    (net (code "95") (name "unconnected-(SW1-NC-Pad1)") (class "Default")
      (node (ref "SW1") (pin "1") (pinfunction "NC_1") (pintype "bidirectional"))
    )
    (net (code "96") (name "unconnected-(SW2-NC-Pad1)") (class "Default")
      (node (ref "SW2") (pin "1") (pinfunction "NC_1") (pintype "bidirectional"))
    )
    (net (code "97") (name "unconnected-(SW3-NC-Pad1)") (class "Default")
      (node (ref "SW3") (pin "1") (pinfunction "NC_1") (pintype "bidirectional"))
    )
    (net (code "98") (name "unconnected-(SW4-NC-Pad1)") (class "Default")
      (node (ref "SW4") (pin "1") (pinfunction "NC_1") (pintype "bidirectional"))
    )
    (net (code "99") (name "unconnected-(SW5-NC-Pad1)") (class "Default")
      (node (ref "SW5") (pin "1") (pinfunction "NC_1") (pintype "bidirectional"))
    )
  )
)
